# Master_Volume_1_55_x_1_95.net
KiCad netlist of a schematic drawn in EAGLE
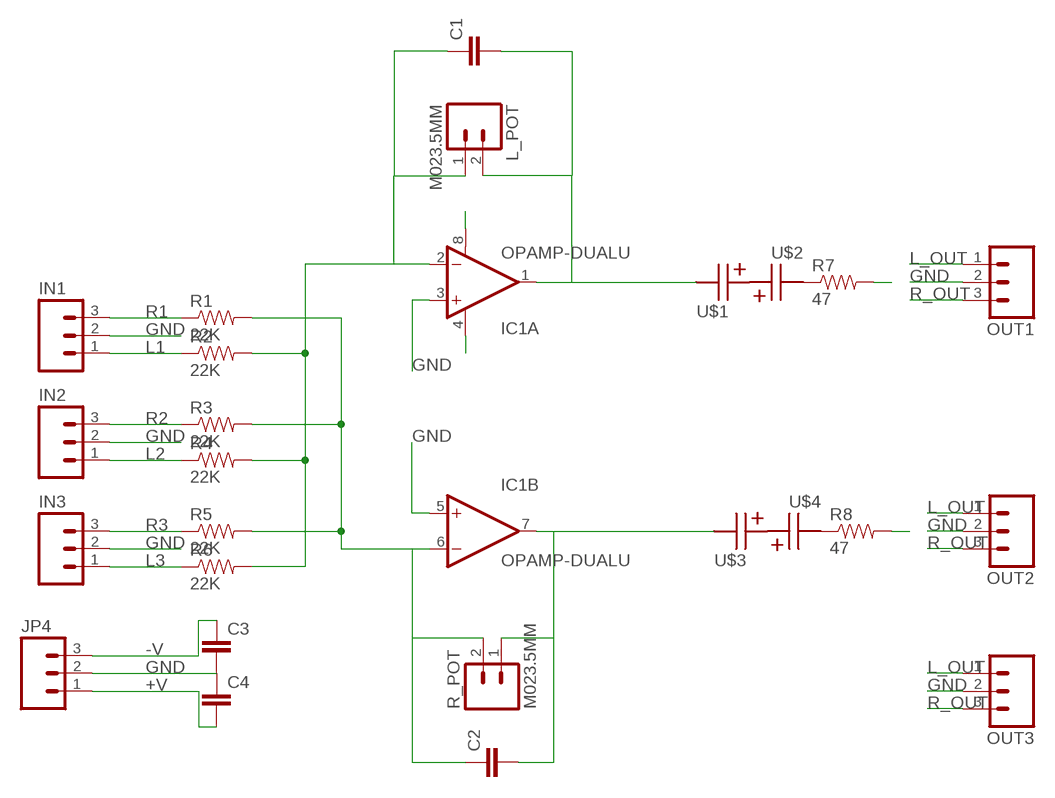
[diagram p0: schematic, sheet 1]

(export (version "E")
  (design (tool "Eeschema 10.0.6"))
  (components
    (comp (ref "C1")
      (value "CAP0805")
      (footprint "eagle-import:0805")
      (libsource (lib "eagle-import") (part "CAP0805"))
    )
    (comp (ref "C2")
      (value "CAP0805")
      (footprint "eagle-import:0805")
      (libsource (lib "eagle-import") (part "CAP0805"))
    )
    (comp (ref "C3")
      (value "CAP1206")
      (footprint "eagle-import:1206")
      (libsource (lib "eagle-import") (part "CAP1206"))
    )
    (comp (ref "C4")
      (value "CAP1206")
      (footprint "eagle-import:1206")
      (libsource (lib "eagle-import") (part "CAP1206"))
    )
    (comp (ref "IC1")
      (value "OPAMP-DUALU")
      (footprint "eagle-import:SO08")
      (libsource (lib "eagle-import") (part "OPAMP-DUALU"))
    )
    (comp (ref "IN1")
      (value "M03SCREW")
      (footprint "eagle-import:SCREWTERMINAL-3.5MM-3")
      (libsource (lib "eagle-import") (part "M03SCREW"))
    )
    (comp (ref "IN2")
      (value "M03SCREW")
      (footprint "eagle-import:SCREWTERMINAL-3.5MM-3")
      (libsource (lib "eagle-import") (part "M03SCREW"))
    )
    (comp (ref "IN3")
      (value "M03SCREW")
      (footprint "eagle-import:SCREWTERMINAL-3.5MM-3")
      (libsource (lib "eagle-import") (part "M03SCREW"))
    )
    (comp (ref "JP4")
      (value "M03SCREW")
      (footprint "eagle-import:SCREWTERMINAL-3.5MM-3")
      (libsource (lib "eagle-import") (part "M03SCREW"))
    )
    (comp (ref "L_POT")
      (value "M023.5MM")
      (footprint "eagle-import:SCREWTERMINAL-3.5MM-2")
      (libsource (lib "eagle-import") (part "M023.5MM"))
    )
    (comp (ref "OUT1")
      (value "M03SCREW")
      (footprint "eagle-import:SCREWTERMINAL-3.5MM-3")
      (libsource (lib "eagle-import") (part "M03SCREW"))
    )
    (comp (ref "OUT2")
      (value "M03SCREW")
      (footprint "eagle-import:SCREWTERMINAL-3.5MM-3")
      (libsource (lib "eagle-import") (part "M03SCREW"))
    )
    (comp (ref "OUT3")
      (value "M03SCREW")
      (footprint "eagle-import:SCREWTERMINAL-3.5MM-3")
      (libsource (lib "eagle-import") (part "M03SCREW"))
    )
    (comp (ref "R1")
      (value "22K")
      (footprint "eagle-import:AXIAL-0.4")
      (libsource (lib "eagle-import") (part "RESISTORPTH-1/4W"))
    )
    (comp (ref "R2")
      (value "22K")
      (footprint "eagle-import:AXIAL-0.4")
      (libsource (lib "eagle-import") (part "RESISTORPTH-1/4W"))
    )
    (comp (ref "R3")
      (value "22K")
      (footprint "eagle-import:AXIAL-0.4")
      (libsource (lib "eagle-import") (part "RESISTORPTH-1/4W"))
    )
    (comp (ref "R4")
      (value "22K")
      (footprint "eagle-import:AXIAL-0.4")
      (libsource (lib "eagle-import") (part "RESISTORPTH-1/4W"))
    )
    (comp (ref "R5")
      (value "22K")
      (footprint "eagle-import:AXIAL-0.4")
      (libsource (lib "eagle-import") (part "RESISTORPTH-1/4W"))
    )
    (comp (ref "R6")
      (value "22K")
      (footprint "eagle-import:AXIAL-0.4")
      (libsource (lib "eagle-import") (part "RESISTORPTH-1/4W"))
    )
    (comp (ref "R7")
      (value "47")
      (footprint "eagle-import:AXIAL-0.4")
      (libsource (lib "eagle-import") (part "RESISTORPTH-1/4W"))
    )
    (comp (ref "R8")
      (value "47")
      (footprint "eagle-import:AXIAL-0.4")
      (libsource (lib "eagle-import") (part "RESISTORPTH-1/4W"))
    )
    (comp (ref "R_POT")
      (value "M023.5MM")
      (footprint "eagle-import:SCREWTERMINAL-3.5MM-2")
      (libsource (lib "eagle-import") (part "M023.5MM"))
    )
    (comp (ref "U$1")
      (value "5MM-12.5MM-POLAR2MMX5MM")
      (footprint "eagle-import:2MMLEAD_5MMDIAMETER")
      (libsource (lib "eagle-import") (part "5MM-12.5MM-POLAR2MMX5MM"))
    )
    (comp (ref "U$2")
      (value "5MM-12.5MM-POLAR2MMX5MM")
      (footprint "eagle-import:2MMLEAD_5MMDIAMETER")
      (libsource (lib "eagle-import") (part "5MM-12.5MM-POLAR2MMX5MM"))
    )
    (comp (ref "U$3")
      (value "5MM-12.5MM-POLAR2MMX5MM")
      (footprint "eagle-import:2MMLEAD_5MMDIAMETER")
      (libsource (lib "eagle-import") (part "5MM-12.5MM-POLAR2MMX5MM"))
    )
    (comp (ref "U$4")
      (value "5MM-12.5MM-POLAR2MMX5MM")
      (footprint "eagle-import:2MMLEAD_5MMDIAMETER")
      (libsource (lib "eagle-import") (part "5MM-12.5MM-POLAR2MMX5MM"))
    )
  )
  (nets
    (net (code "1") (name "/+V") (class "Default")
      (node (ref "C4") (pin "2") (pinfunction "2_2") (pintype "passive"))
      (node (ref "IC1") (pin "8") (pinfunction "V+_8") (pintype "power_in"))
      (node (ref "JP4") (pin "1") (pinfunction "1_1") (pintype "passive"))
    )
    (net (code "2") (name "/-V") (class "Default")
      (node (ref "C3") (pin "1") (pinfunction "1_1") (pintype "passive"))
      (node (ref "IC1") (pin "4") (pinfunction "V-_4") (pintype "power_in"))
      (node (ref "JP4") (pin "3") (pinfunction "3_3") (pintype "passive"))
    )
    (net (code "3") (name "/GND") (class "Default")
      (node (ref "C3") (pin "2") (pinfunction "2_2") (pintype "passive"))
      (node (ref "C4") (pin "1") (pinfunction "1_1") (pintype "passive"))
      (node (ref "IC1") (pin "3") (pinfunction "+IN_3") (pintype "input"))
      (node (ref "IC1") (pin "5") (pinfunction "+IN_5") (pintype "input"))
      (node (ref "IN1") (pin "2") (pinfunction "2_2") (pintype "passive"))
      (node (ref "IN2") (pin "2") (pinfunction "2_2") (pintype "passive"))
      (node (ref "IN3") (pin "2") (pinfunction "2_2") (pintype "passive"))
      (node (ref "JP4") (pin "2") (pinfunction "2_2") (pintype "passive"))
      (node (ref "OUT1") (pin "2") (pinfunction "2_2") (pintype "passive"))
      (node (ref "OUT2") (pin "2") (pinfunction "2_2") (pintype "passive"))
      (node (ref "OUT3") (pin "2") (pinfunction "2_2") (pintype "passive"))
    )
    (net (code "4") (name "/L1") (class "Default")
      (node (ref "IN1") (pin "1") (pinfunction "1_1") (pintype "passive"))
      (node (ref "R2") (pin "P$1") (pinfunction "1_P$1") (pintype "passive"))
    )
    (net (code "5") (name "/L2") (class "Default")
      (node (ref "IN2") (pin "1") (pinfunction "1_1") (pintype "passive"))
      (node (ref "R4") (pin "P$1") (pinfunction "1_P$1") (pintype "passive"))
    )
    (net (code "6") (name "/L3") (class "Default")
      (node (ref "IN3") (pin "1") (pinfunction "1_1") (pintype "passive"))
      (node (ref "R6") (pin "P$1") (pinfunction "1_P$1") (pintype "passive"))
    )
    (net (code "7") (name "/L_OUT") (class "Default")
      (node (ref "OUT1") (pin "1") (pinfunction "1_1") (pintype "passive"))
      (node (ref "OUT2") (pin "1") (pinfunction "1_1") (pintype "passive"))
      (node (ref "OUT3") (pin "1") (pinfunction "1_1") (pintype "passive"))
      (node (ref "R7") (pin "P$2") (pinfunction "2_P$2") (pintype "passive"))
    )
    (net (code "8") (name "/R1") (class "Default")
      (node (ref "IN1") (pin "3") (pinfunction "3_3") (pintype "passive"))
      (node (ref "R1") (pin "P$1") (pinfunction "1_P$1") (pintype "passive"))
    )
    (net (code "9") (name "/R2") (class "Default")
      (node (ref "IN2") (pin "3") (pinfunction "3_3") (pintype "passive"))
      (node (ref "R3") (pin "P$1") (pinfunction "1_P$1") (pintype "passive"))
    )
    (net (code "10") (name "/R3") (class "Default")
      (node (ref "IN3") (pin "3") (pinfunction "3_3") (pintype "passive"))
      (node (ref "R5") (pin "P$1") (pinfunction "1_P$1") (pintype "passive"))
    )
    (net (code "11") (name "/R_OUT") (class "Default")
      (node (ref "OUT1") (pin "3") (pinfunction "3_3") (pintype "passive"))
      (node (ref "OUT2") (pin "3") (pinfunction "3_3") (pintype "passive"))
      (node (ref "OUT3") (pin "3") (pinfunction "3_3") (pintype "passive"))
      (node (ref "R8") (pin "P$2") (pinfunction "2_P$2") (pintype "passive"))
    )
    (net (code "12") (name "Net-(IC1A--IN)") (class "Default")
      (node (ref "C1") (pin "1") (pinfunction "1_1") (pintype "passive"))
      (node (ref "IC1") (pin "2") (pinfunction "-IN_2") (pintype "input"))
      (node (ref "L_POT") (pin "1") (pinfunction "1_1") (pintype "passive"))
      (node (ref "R2") (pin "P$2") (pinfunction "2_P$2") (pintype "passive"))
      (node (ref "R4") (pin "P$2") (pinfunction "2_P$2") (pintype "passive"))
      (node (ref "R6") (pin "P$2") (pinfunction "2_P$2") (pintype "passive"))
    )
    (net (code "13") (name "Net-(IC1A-OUT)") (class "Default")
      (node (ref "C1") (pin "2") (pinfunction "2_2") (pintype "passive"))
      (node (ref "IC1") (pin "1") (pinfunction "OUT_1") (pintype "output"))
      (node (ref "L_POT") (pin "2") (pinfunction "2_2") (pintype "passive"))
      (node (ref "U$1") (pin "+") (pinfunction "-_+") (pintype "bidirectional"))
    )
    (net (code "14") (name "Net-(IC1B--IN)") (class "Default")
      (node (ref "C2") (pin "1") (pinfunction "1_1") (pintype "passive"))
      (node (ref "IC1") (pin "6") (pinfunction "-IN_6") (pintype "input"))
      (node (ref "R1") (pin "P$2") (pinfunction "2_P$2") (pintype "passive"))
      (node (ref "R3") (pin "P$2") (pinfunction "2_P$2") (pintype "passive"))
      (node (ref "R5") (pin "P$2") (pinfunction "2_P$2") (pintype "passive"))
      (node (ref "R_POT") (pin "2") (pinfunction "2_2") (pintype "passive"))
    )
    (net (code "15") (name "Net-(IC1B-OUT)") (class "Default")
      (node (ref "C2") (pin "2") (pinfunction "2_2") (pintype "passive"))
      (node (ref "IC1") (pin "7") (pinfunction "OUT_7") (pintype "output"))
      (node (ref "R_POT") (pin "1") (pinfunction "1_1") (pintype "passive"))
      (node (ref "U$3") (pin "+") (pinfunction "-_+") (pintype "bidirectional"))
    )
    (net (code "16") (name "Net-(R7-1)") (class "Default")
      (node (ref "R7") (pin "P$1") (pinfunction "1_P$1") (pintype "passive"))
      (node (ref "U$2") (pin "+") (pinfunction "-_+") (pintype "bidirectional"))
    )
    (net (code "17") (name "Net-(R8-1)") (class "Default")
      (node (ref "R8") (pin "P$1") (pinfunction "1_P$1") (pintype "passive"))
      (node (ref "U$4") (pin "+") (pinfunction "-_+") (pintype "bidirectional"))
    )
    (net (code "18") (name "Net-(U$1-+)") (class "Default")
      (node (ref "U$1") (pin "-") (pinfunction "+_-") (pintype "bidirectional"))
      (node (ref "U$2") (pin "-") (pinfunction "+_-") (pintype "bidirectional"))
    )
    (net (code "19") (name "Net-(U$3-+)") (class "Default")
      (node (ref "U$3") (pin "-") (pinfunction "+_-") (pintype "bidirectional"))
      (node (ref "U$4") (pin "-") (pinfunction "+_-") (pintype "bidirectional"))
    )
  )
)
